# Dingo_Schematic.net
KiCad netlist of a schematic drawn in Altium Designer
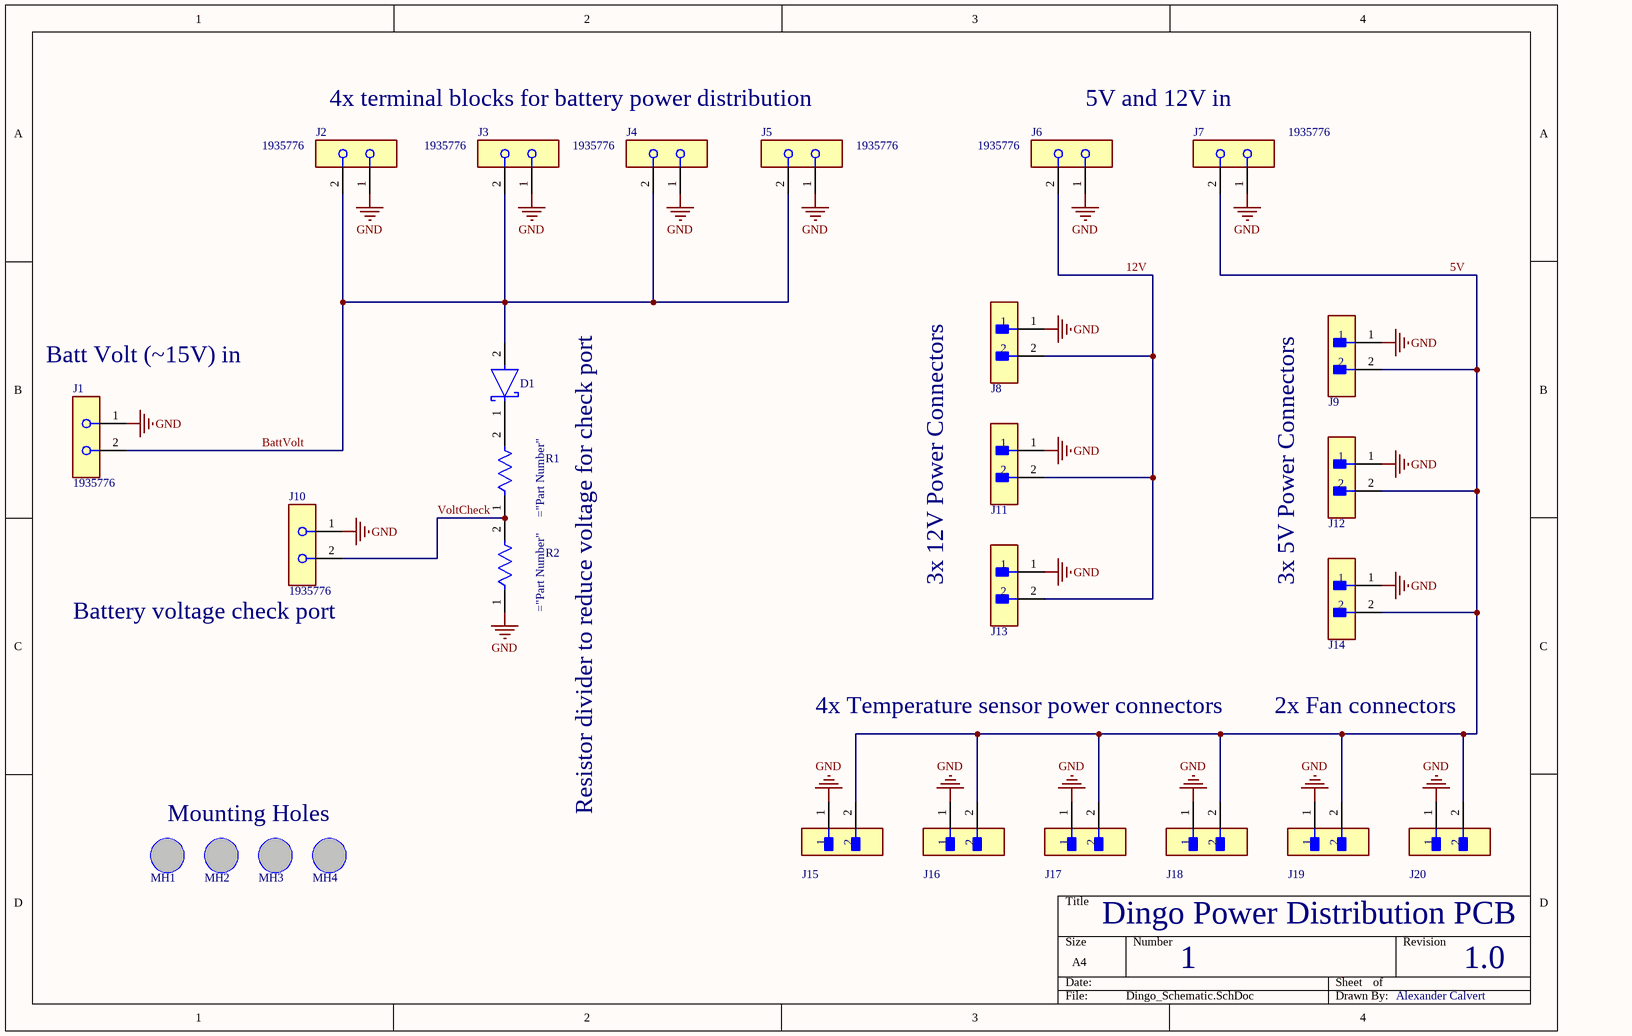
[diagram p0: Dingo_Schematic.SchDoc]

(export (version "E")
  (design (tool "Eeschema 10.0.6"))
  (components
    (comp (ref "D1")
      (value "Diode")
      (footprint "Diodes_Inc_SMA_MFG")
      (libsource (lib "Diode_Diodes_Inc_B160-13-F_eec") (part "B160-13-F"))
    )
    (comp (ref "J1")
      (value "battery Input")
      (footprint "Phoenix_Contact_1935776_0")
      (description "CONN 2 Position Wire to Board Terminal Block Horizontal with Board 0.197\" (5.00mm) Through Hole")
      (fields
        (field (name "PART NUMBER") "1935776")
        (field (name "VOLTAGE") "300V")
        (field (name "MANUFACTURER") "Phoenix Contact")
      )
      (libsource (lib "") (part "Conn_Phoenix_Contact_1935776_eec_1"))
    )
    (comp (ref "J2")
      (value "Spare connector")
      (footprint "Phoenix_Contact_1935776_0")
      (description "CONN 2 Position Wire to Board Terminal Block Horizontal with Board 0.197\" (5.00mm) Through Hole")
      (fields
        (field (name "PART NUMBER") "1935776")
        (field (name "VOLTAGE") "300V")
        (field (name "MANUFACTURER") "Phoenix Contact")
      )
      (libsource (lib "Conn_Phoenix_Contact_1935776_eec") (part "Conn_Phoenix_Contact_1935776_eec"))
    )
    (comp (ref "J3")
      (value "To 7.8V rail")
      (footprint "Phoenix_Contact_1935776_0")
      (description "CONN 2 Position Wire to Board Terminal Block Horizontal with Board 0.197\" (5.00mm) Through Hole")
      (fields
        (field (name "PART NUMBER") "1935776")
        (field (name "VOLTAGE") "300V")
        (field (name "MANUFACTURER") "Phoenix Contact")
      )
      (libsource (lib "Conn_Phoenix_Contact_1935776_eec") (part "Conn_Phoenix_Contact_1935776_eec"))
    )
    (comp (ref "J4")
      (value "To 5V rail")
      (footprint "Phoenix_Contact_1935776_0")
      (description "CONN 2 Position Wire to Board Terminal Block Horizontal with Board 0.197\" (5.00mm) Through Hole")
      (fields
        (field (name "PART NUMBER") "1935776")
        (field (name "VOLTAGE") "300V")
        (field (name "MANUFACTURER") "Phoenix Contact")
      )
      (libsource (lib "Conn_Phoenix_Contact_1935776_eec") (part "Conn_Phoenix_Contact_1935776_eec"))
    )
    (comp (ref "J5")
      (value "To 12V rail")
      (footprint "Phoenix_Contact_1935776_0")
      (description "CONN 2 Position Wire to Board Terminal Block Horizontal with Board 0.197\" (5.00mm) Through Hole")
      (fields
        (field (name "PART NUMBER") "1935776")
        (field (name "VOLTAGE") "300V")
        (field (name "MANUFACTURER") "Phoenix Contact")
      )
      (libsource (lib "Conn_Phoenix_Contact_1935776_eec") (part "Conn_Phoenix_Contact_1935776_eec"))
    )
    (comp (ref "J6")
      (value "12V rail return")
      (footprint "Phoenix_Contact_1935776_0")
      (description "CONN 2 Position Wire to Board Terminal Block Horizontal with Board 0.197\" (5.00mm) Through Hole")
      (fields
        (field (name "PART NUMBER") "1935776")
        (field (name "VOLTAGE") "300V")
        (field (name "MANUFACTURER") "Phoenix Contact")
      )
      (libsource (lib "Conn_Phoenix_Contact_1935776_eec") (part "Conn_Phoenix_Contact_1935776_eec"))
    )
    (comp (ref "J7")
      (value "5V rail return")
      (footprint "Phoenix_Contact_1935776_0")
      (description "CONN 2 Position Wire to Board Terminal Block Horizontal with Board 0.197\" (5.00mm) Through Hole")
      (fields
        (field (name "PART NUMBER") "1935776")
        (field (name "VOLTAGE") "300V")
        (field (name "MANUFACTURER") "Phoenix Contact")
      )
      (libsource (lib "Conn_Phoenix_Contact_1935776_eec") (part "Conn_Phoenix_Contact_1935776_eec"))
    )
    (comp (ref "J8")
      (value "12Vout1")
      (footprint "JST_0_MFG")
      (libsource (lib "") (part "B2B-PH-K-S_LF_SN_1"))
    )
    (comp (ref "J9")
      (value "5Vout1")
      (footprint "JST_0_MFG")
      (libsource (lib "") (part "B2B-PH-K-S_LF_SN_1"))
    )
    (comp (ref "J10")
      (value "TeensyADCport")
      (footprint "Phoenix_Contact_1935776_0")
      (description "CONN 2 Position Wire to Board Terminal Block Horizontal with Board 0.197\" (5.00mm) Through Hole")
      (fields
        (field (name "PART NUMBER") "1935776")
        (field (name "VOLTAGE") "300V")
        (field (name "MANUFACTURER") "Phoenix Contact")
      )
      (libsource (lib "") (part "Conn_Phoenix_Contact_1935776_eec_1"))
    )
    (comp (ref "J11")
      (value "12Vout2")
      (footprint "JST_0_MFG")
      (libsource (lib "") (part "B2B-PH-K-S_LF_SN_1"))
    )
    (comp (ref "J12")
      (value "5Vout2")
      (footprint "JST_0_MFG")
      (libsource (lib "") (part "B2B-PH-K-S_LF_SN_1"))
    )
    (comp (ref "J13")
      (value "12Vout3")
      (footprint "JST_0_MFG")
      (libsource (lib "") (part "B2B-PH-K-S_LF_SN_1"))
    )
    (comp (ref "J14")
      (value "5Vout3")
      (footprint "JST_0_MFG")
      (libsource (lib "") (part "B2B-PH-K-S_LF_SN_1"))
    )
    (comp (ref "J15")
      (value "Temp1")
      (footprint "JST_0_MFG")
      (libsource (lib "Conn_JST_B2B-PH-K-S_LF_SN_eec") (part "B2B-PH-K-S_LF_SN"))
    )
    (comp (ref "J16")
      (value "Temp2")
      (footprint "JST_0_MFG")
      (libsource (lib "Conn_JST_B2B-PH-K-S_LF_SN_eec") (part "B2B-PH-K-S_LF_SN"))
    )
    (comp (ref "J17")
      (value "Temp3")
      (footprint "JST_0_MFG")
      (libsource (lib "Conn_JST_B2B-PH-K-S_LF_SN_eec") (part "B2B-PH-K-S_LF_SN"))
    )
    (comp (ref "J18")
      (value "Temp4")
      (footprint "JST_0_MFG")
      (libsource (lib "Conn_JST_B2B-PH-K-S_LF_SN_eec") (part "B2B-PH-K-S_LF_SN"))
    )
    (comp (ref "J19")
      (value "Fan1")
      (footprint "JST_0_MFG")
      (libsource (lib "Conn_JST_B2B-PH-K-S_LF_SN_eec") (part "B2B-PH-K-S_LF_SN"))
    )
    (comp (ref "J20")
      (value "Fan2")
      (footprint "JST_0_MFG")
      (libsource (lib "Conn_JST_B2B-PH-K-S_LF_SN_eec") (part "B2B-PH-K-S_LF_SN"))
    )
    (comp (ref "MH1")
      (value "Mounting Hole Non-Plated 3.2mm")
      (footprint "MH3.2mm")
      (description "Mounting Hole Non-Plated 3.2mm drill hole")
      (libsource (lib "MH3.2") (part "MH3P2MM"))
    )
    (comp (ref "MH2")
      (value "Mounting Hole Non-Plated 3.2mm")
      (footprint "MH3.2mm")
      (description "Mounting Hole Non-Plated 3.2mm drill hole")
      (libsource (lib "MH3.2") (part "MH3P2MM"))
    )
    (comp (ref "MH3")
      (value "Mounting Hole Non-Plated 3.2mm")
      (footprint "MH3.2mm")
      (description "Mounting Hole Non-Plated 3.2mm drill hole")
      (libsource (lib "MH3.2") (part "MH3P2MM"))
    )
    (comp (ref "MH4")
      (value "Mounting Hole Non-Plated 3.2mm")
      (footprint "MH3.2mm")
      (description "Mounting Hole Non-Plated 3.2mm drill hole")
      (libsource (lib "MH3.2") (part "MH3P2MM"))
    )
    (comp (ref "R1")
      (value "47k")
      (footprint "TE_Connectivity_CRGCQ1206_IPC_A")
      (libsource (lib "Res_TE_Connectivity_CRGCQ1206F47K_eec") (part "CRGCQ1206F47K"))
    )
    (comp (ref "R2")
      (value "10k")
      (footprint "Res_TE_Connectivity_CRGCQ0805F10K_eec_IPC_A:TE_Connectivity_CRGCQ0805_IPC_A")
      (libsource (lib "Res_TE_Connectivity_CRGCQ0805F10K_eec") (part "CRGCQ0805F10K"))
    )
  )
  (nets
    (net (code "1") (name "/5V") (class "Default")
      (node (ref "J12") (pin "2") (pinfunction "2_2") (pintype "passive"))
      (node (ref "J14") (pin "2") (pinfunction "2_2") (pintype "passive"))
      (node (ref "J15") (pin "2") (pinfunction "2_2") (pintype "passive"))
      (node (ref "J16") (pin "2") (pinfunction "2_2") (pintype "passive"))
      (node (ref "J17") (pin "2") (pinfunction "2_2") (pintype "passive"))
      (node (ref "J18") (pin "2") (pinfunction "2_2") (pintype "passive"))
      (node (ref "J19") (pin "2") (pinfunction "2_2") (pintype "passive"))
      (node (ref "J20") (pin "2") (pinfunction "2_2") (pintype "passive"))
      (node (ref "J7") (pin "2") (pinfunction "2_2") (pintype "passive"))
      (node (ref "J9") (pin "2") (pinfunction "2_2") (pintype "passive"))
    )
    (net (code "2") (name "/12V") (class "Default")
      (node (ref "J11") (pin "2") (pinfunction "2_2") (pintype "passive"))
      (node (ref "J13") (pin "2") (pinfunction "2_2") (pintype "passive"))
      (node (ref "J6") (pin "2") (pinfunction "2_2") (pintype "passive"))
      (node (ref "J8") (pin "2") (pinfunction "2_2") (pintype "passive"))
    )
    (net (code "3") (name "/BattVolt") (class "Default")
      (node (ref "D1") (pin "2") (pinfunction "A_2") (pintype "passive"))
      (node (ref "J1") (pin "2") (pinfunction "2_2") (pintype "passive"))
      (node (ref "J2") (pin "2") (pinfunction "2_2") (pintype "passive"))
      (node (ref "J3") (pin "2") (pinfunction "2_2") (pintype "passive"))
      (node (ref "J4") (pin "2") (pinfunction "2_2") (pintype "passive"))
      (node (ref "J5") (pin "2") (pinfunction "2_2") (pintype "passive"))
    )
    (net (code "4") (name "/VoltCheck") (class "Default")
      (node (ref "J10") (pin "2") (pinfunction "2_2") (pintype "passive"))
      (node (ref "R1") (pin "1") (pinfunction "1_1") (pintype "passive"))
      (node (ref "R2") (pin "2") (pinfunction "2_2") (pintype "passive"))
    )
    (net (code "5") (name "GND") (class "Default")
      (node (ref "J1") (pin "1") (pinfunction "1_1") (pintype "passive"))
      (node (ref "J10") (pin "1") (pinfunction "1_1") (pintype "passive"))
      (node (ref "J11") (pin "1") (pinfunction "1_1") (pintype "passive"))
      (node (ref "J12") (pin "1") (pinfunction "1_1") (pintype "passive"))
      (node (ref "J13") (pin "1") (pinfunction "1_1") (pintype "passive"))
      (node (ref "J14") (pin "1") (pinfunction "1_1") (pintype "passive"))
      (node (ref "J15") (pin "1") (pinfunction "1_1") (pintype "passive"))
      (node (ref "J16") (pin "1") (pinfunction "1_1") (pintype "passive"))
      (node (ref "J17") (pin "1") (pinfunction "1_1") (pintype "passive"))
      (node (ref "J18") (pin "1") (pinfunction "1_1") (pintype "passive"))
      (node (ref "J19") (pin "1") (pinfunction "1_1") (pintype "passive"))
      (node (ref "J2") (pin "1") (pinfunction "1_1") (pintype "passive"))
      (node (ref "J20") (pin "1") (pinfunction "1_1") (pintype "passive"))
      (node (ref "J3") (pin "1") (pinfunction "1_1") (pintype "passive"))
      (node (ref "J4") (pin "1") (pinfunction "1_1") (pintype "passive"))
      (node (ref "J5") (pin "1") (pinfunction "1_1") (pintype "passive"))
      (node (ref "J6") (pin "1") (pinfunction "1_1") (pintype "passive"))
      (node (ref "J7") (pin "1") (pinfunction "1_1") (pintype "passive"))
      (node (ref "J8") (pin "1") (pinfunction "1_1") (pintype "passive"))
      (node (ref "J9") (pin "1") (pinfunction "1_1") (pintype "passive"))
      (node (ref "R2") (pin "1") (pinfunction "1_1") (pintype "passive"))
    )
    (net (code "6") (name "Net-(D1-C)") (class "Default")
      (node (ref "D1") (pin "1") (pinfunction "C_1") (pintype "passive"))
      (node (ref "R1") (pin "2") (pinfunction "2_2") (pintype "passive"))
    )
  )
)
